# Sheet3.net
KiCad netlist of a schematic drawn in Altium Designer
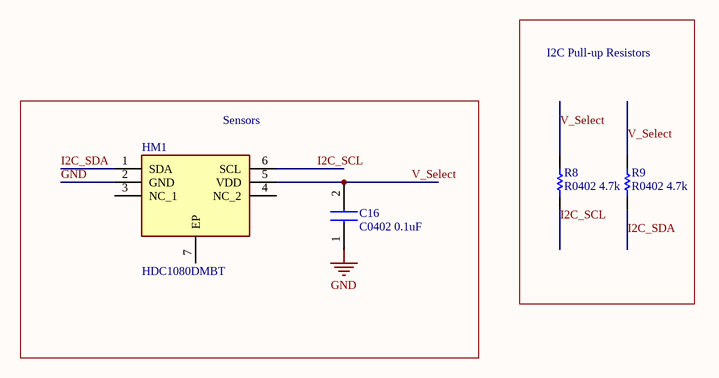
[diagram p0: Sheet3.SchDoc]

(export (version "E")
  (design (tool "Eeschema 10.0.6"))
  (components
    (comp (ref "C16")
      (value "C0402 0.1uF")
      (footprint "SamacSys:CAPC0603X33N")
      (description "Capacitor")
      (fields
        (field (name "MANUFACTURER_PART_NUMBER") "02014D474MAT2A")
        (field (name "MOUSER PART NUMBER") "581-02014D474MAT2A")
      )
      (libsource (lib "*") (part "02014D474MAT2A"))
    )
    (comp (ref "HM1")
      (value "HDC1080DMBT")
      (footprint "SON100P300X300X80-7N")
      (description "Hygrometer")
      (fields
        (field (name "MOUSER PART NUMBER") "595-HDC1080DMBT")
        (field (name "RS PART NUMBER") "1330170P")
      )
      (libsource (lib "EnvironmentalSensor") (part "HDC1080DMBT"))
    )
    (comp (ref "R8")
      (value "R0402 4.7k")
      (footprint "RESC1005X40X25NL05T05")
      (fields (field (name "MANUFACTURER") "Vishay Dale") (field (name "PART NUMBER") "CRCW040210K0FKED"))
      (libsource (lib "Altium Content Vault") (part "RES"))
    )
    (comp (ref "R9")
      (value "R0402 4.7k")
      (footprint "RESC1005X40X25NL05T05")
      (fields (field (name "MANUFACTURER") "Vishay Dale") (field (name "PART NUMBER") "CRCW040210K0FKED"))
      (libsource (lib "Altium Content Vault") (part "RES"))
    )
  )
  (nets
    (net (code "1") (name "/I2C_SCL") (class "Default")
      (node (ref "HM1") (pin "6") (pinfunction "SCL_6") (pintype "passive"))
      (node (ref "R8") (pin "1") (pinfunction "1_1") (pintype "passive"))
    )
    (net (code "2") (name "/I2C_SDA") (class "Default")
      (node (ref "HM1") (pin "1") (pinfunction "SDA_1") (pintype "passive"))
      (node (ref "R9") (pin "1") (pinfunction "1_1") (pintype "passive"))
    )
    (net (code "3") (name "/V_Select") (class "Default")
      (node (ref "C16") (pin "2") (pinfunction "2_2") (pintype "passive"))
      (node (ref "HM1") (pin "5") (pinfunction "VDD_5") (pintype "power_in"))
      (node (ref "R8") (pin "2") (pinfunction "2_2") (pintype "passive"))
      (node (ref "R9") (pin "2") (pinfunction "2_2") (pintype "passive"))
    )
    (net (code "4") (name "GND") (class "Default")
      (node (ref "C16") (pin "1") (pinfunction "1_1") (pintype "passive"))
      (node (ref "HM1") (pin "2") (pinfunction "GND_2") (pintype "power_in"))
    )
    (net (code "5") (name "unconnected-(HM1-EP-Pad7)") (class "Default")
      (node (ref "HM1") (pin "7") (pinfunction "EP_7") (pintype "power_in"))
    )
    (net (code "6") (name "unconnected-(HM1-NC_1-Pad3)") (class "Default")
      (node (ref "HM1") (pin "3") (pinfunction "NC_1_3") (pintype "passive"))
    )
    (net (code "7") (name "unconnected-(HM1-NC_2-Pad4)") (class "Default")
      (node (ref "HM1") (pin "4") (pinfunction "NC_2_4") (pintype "passive"))
    )
  )
)
